# USB_Downloader_V1_2.net
KiCad netlist of a schematic drawn in Altium Designer
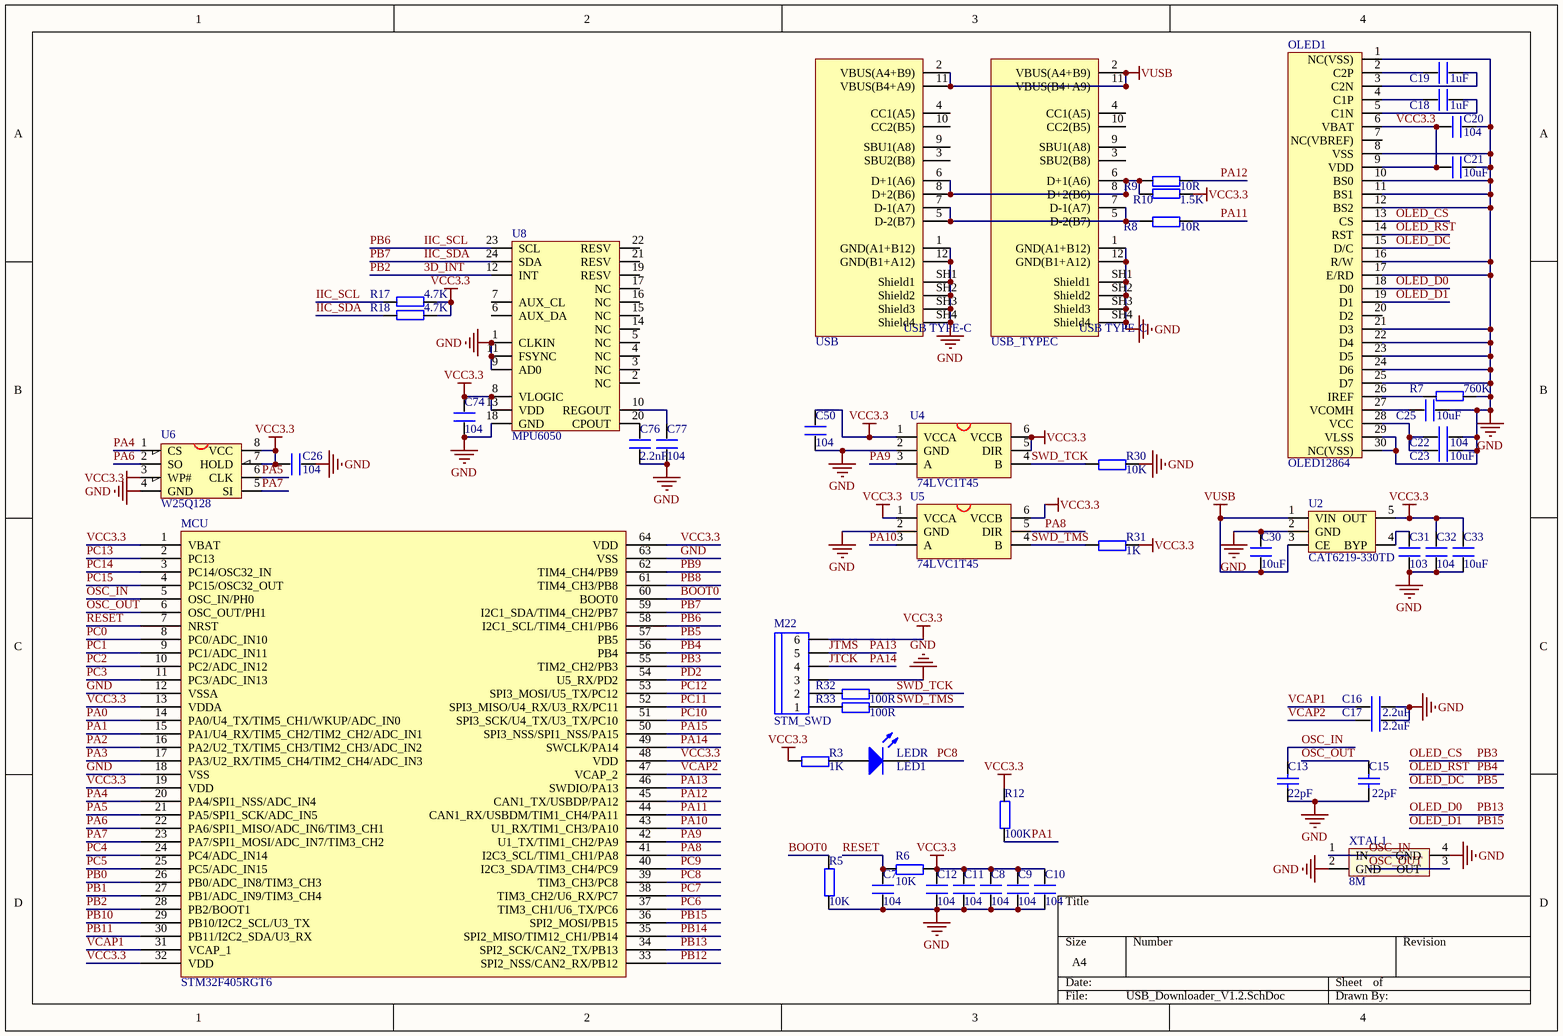
[diagram p0: USB_Downloader_V1.2.SchDoc]

(export (version "E")
  (design (tool "Eeschema 10.0.6"))
  (components
    (comp (ref "C7")
      (value "104")
      (footprint "C 0603_L")
      (libsource (lib "WarShip V3 STM32103封装库") (part "C"))
    )
    (comp (ref "C8")
      (value "104")
      (footprint "C 0603_L")
      (libsource (lib "WarShip V3 STM32103封装库") (part "C"))
    )
    (comp (ref "C9")
      (value "104")
      (footprint "C 0603_L")
      (libsource (lib "WarShip V3 STM32103封装库") (part "C"))
    )
    (comp (ref "C10")
      (value "104")
      (footprint "C 0603_L")
      (libsource (lib "WarShip V3 STM32103封装库") (part "C"))
    )
    (comp (ref "C11")
      (value "104")
      (footprint "C 0603_L")
      (libsource (lib "WarShip V3 STM32103封装库") (part "C"))
    )
    (comp (ref "C12")
      (value "104")
      (footprint "C 0603_L")
      (libsource (lib "WarShip V3 STM32103封装库") (part "C"))
    )
    (comp (ref "C13") (value "22pF") (footprint "C 0603_L") (libsource (lib "L476") (part "CAP")))
    (comp (ref "C15") (value "22pF") (footprint "C 0603_L") (libsource (lib "L476") (part "CAP")))
    (comp (ref "C16")
      (value "2.2uF")
      (footprint "C 0603_L")
      (libsource (lib "WarShip V3 STM32103封装库") (part "C"))
    )
    (comp (ref "C17")
      (value "2.2uF")
      (footprint "C 0603_L")
      (libsource (lib "WarShip V3 STM32103封装库") (part "C"))
    )
    (comp (ref "C18")
      (value "1uF")
      (footprint "C 0603_L")
      (libsource (lib "WarShip V3 STM32103封装库") (part "C"))
    )
    (comp (ref "C19")
      (value "1uF")
      (footprint "C 0603_L")
      (libsource (lib "WarShip V3 STM32103封装库") (part "C"))
    )
    (comp (ref "C20")
      (value "104")
      (footprint "C 0603_L")
      (libsource (lib "WarShip V3 STM32103封装库") (part "C"))
    )
    (comp (ref "C21")
      (value "10uF")
      (footprint "C 0603_L")
      (libsource (lib "WarShip V3 STM32103封装库") (part "C"))
    )
    (comp (ref "C22")
      (value "104")
      (footprint "C 0603_L")
      (libsource (lib "WarShip V3 STM32103封装库") (part "C"))
    )
    (comp (ref "C23")
      (value "10uF")
      (footprint "C 0603_L")
      (libsource (lib "WarShip V3 STM32103封装库") (part "C"))
    )
    (comp (ref "C25")
      (value "10uF")
      (footprint "C 0603_L")
      (libsource (lib "WarShip V3 STM32103封装库") (part "C"))
    )
    (comp (ref "C26")
      (value "104")
      (footprint "C 0603_L")
      (libsource (lib "WarShip V3 STM32103封装库") (part "C"))
    )
    (comp (ref "C30")
      (value "10uF")
      (footprint "C 0603_L")
      (libsource (lib "WarShip V3 STM32103封装库") (part "C"))
    )
    (comp (ref "C31")
      (value "103")
      (footprint "C 0603_L")
      (libsource (lib "WarShip V3 STM32103封装库") (part "C"))
    )
    (comp (ref "C32")
      (value "104")
      (footprint "C 0603_L")
      (libsource (lib "WarShip V3 STM32103封装库") (part "C"))
    )
    (comp (ref "C33")
      (value "10uF")
      (footprint "C 0603_L")
      (libsource (lib "WarShip V3 STM32103封装库") (part "C"))
    )
    (comp (ref "C50")
      (value "104")
      (footprint "C 0603_L")
      (libsource (lib "WarShip V3 STM32103封装库") (part "C"))
    )
    (comp (ref "C74") (value "104") (footprint "C 0603_L") (libsource (lib "MYCOMLIB") (part "C")))
    (comp (ref "C76") (value "2.2nF") (footprint "C 0603_L") (libsource (lib "MYCOMLIB") (part "C")))
    (comp (ref "C77") (value "104") (footprint "C 0603_L") (libsource (lib "MYCOMLIB") (part "C")))
    (comp (ref "LEDR")
      (value "LED1")
      (footprint "LED 0805B")
      (description "Typical RED, GREEN, YELLOW, AMBER GaAs LED")
      (fields (field (name "PUBLISHER") "Altium Limited"))
      (libsource (lib "阿波罗STM32F4&F7底板封装库") (part "LED2"))
    )
    (comp (ref "M22") (value "STM_SWD") (footprint "SH1.0-6P") (libsource (lib "MiniFly ") (part "HEAD6")))
    (comp (ref "MCU")
      (value "STM32F405RGT6")
      (footprint "LQFP64 10X10_L")
      (description "Flaah:256/RAM:48/IO:51")
      (libsource (lib "ATKF405 V1.1") (part "STM32F405RGT6"))
    )
    (comp (ref "OLED1")
      (value "OLED12864")
      (footprint "OLED_0.96")
      (libsource (lib "OLED模块封装库") (part "OLED12864"))
    )
    (comp (ref "R3")
      (value "1K")
      (footprint "R 0603_L")
      (libsource (lib "WarShip V3 STM32103封装库") (part "R"))
    )
    (comp (ref "R5")
      (value "10K")
      (footprint "R 0603_L")
      (libsource (lib "WarShip V3 STM32103封装库") (part "R"))
    )
    (comp (ref "R6")
      (value "10K")
      (footprint "R 0603_L")
      (libsource (lib "WarShip V3 STM32103封装库") (part "R"))
    )
    (comp (ref "R7")
      (value "760K")
      (footprint "R 0603_L")
      (libsource (lib "WarShip V3 STM32103封装库") (part "R"))
    )
    (comp (ref "R8")
      (value "10R")
      (footprint "R 0603_L")
      (libsource (lib "WarShip V3 STM32103封装库") (part "R"))
    )
    (comp (ref "R9")
      (value "10R")
      (footprint "R 0603_L")
      (libsource (lib "WarShip V3 STM32103封装库") (part "R"))
    )
    (comp (ref "R10")
      (value "1.5K")
      (footprint "R 0603_L")
      (libsource (lib "WarShip V3 STM32103封装库") (part "R"))
    )
    (comp (ref "R12")
      (value "100K")
      (footprint "R 0603_L")
      (libsource (lib "WarShip V3 STM32103封装库") (part "R"))
    )
    (comp (ref "R17")
      (value "4.7K")
      (footprint "R 0603_L")
      (libsource (lib "WarShip V3 STM32103封装库") (part "R"))
    )
    (comp (ref "R18")
      (value "4.7K")
      (footprint "R 0603_L")
      (libsource (lib "WarShip V3 STM32103封装库") (part "R"))
    )
    (comp (ref "R30")
      (value "10K")
      (footprint "R 0603_L")
      (libsource (lib "WarShip V3 STM32103封装库") (part "R"))
    )
    (comp (ref "R31")
      (value "1K")
      (footprint "R 0603_L")
      (libsource (lib "WarShip V3 STM32103封装库") (part "R"))
    )
    (comp (ref "R32")
      (value "100R")
      (footprint "R 0603_L")
      (libsource (lib "WarShip V3 STM32103封装库") (part "R"))
    )
    (comp (ref "R33")
      (value "100R")
      (footprint "R 0603_L")
      (libsource (lib "WarShip V3 STM32103封装库") (part "R"))
    )
    (comp (ref "U2")
      (value "CAT6219-330TD")
      (footprint "SOT23-5L")
      (description "3.3V 500mA LDO")
      (libsource (lib "STM32H743核心板封装库") (part "CAT6219-330TD"))
    )
    (comp (ref "U4")
      (value "74LVC1T45")
      (footprint "SOT363-6L")
      (description "1路双向电平转换")
      (libsource (lib "LovelessingSch") (part "74LVC1T45"))
    )
    (comp (ref "U5")
      (value "74LVC1T45")
      (footprint "SOT363-6L")
      (description "1路双向电平转换")
      (libsource (lib "LovelessingSch") (part "74LVC1T45"))
    )
    (comp (ref "U6")
      (value "W25Q128")
      (footprint "SOP8W_L")
      (description "W25X16;SST25VF016;MX25L1605")
      (libsource (lib "WarShip V3 STM32103封装库") (part "W25X16"))
    )
    (comp (ref "U8")
      (value "MPU6050")
      (footprint "QFN24 4x4_N")
      (description "9轴运动处理传感器")
      (libsource (lib "ALIENTEK_COMPONENT") (part "MPU6050"))
    )
    (comp (ref "USB")
      (value "USB TypeC")
      (footprint "USB Type-C")
      (description "12P TypeC 母座")
      (libsource (lib "ESP32_Weather") (part "USB Type-C"))
    )
    (comp (ref "USB_TYPEC")
      (value "USB TypeC")
      (footprint "USB Type-C")
      (description "12P TypeC 母座")
      (libsource (lib "ESP32_Weather") (part "USB Type-C"))
    )
    (comp (ref "XTAL1")
      (value "8M")
      (footprint "XTAL3225   无源")
      (description "无源贴片晶振")
      (libsource (lib "REMOTOR") (part "XTAL-无源贴片"))
    )
  )
  (nets
    (net (code "1") (name "/3D_INT") (class "Default")
      (node (ref "MCU") (pin "28") (pinfunction "PB2/BOOT1_28") (pintype "passive"))
      (node (ref "U8") (pin "12") (pinfunction "INT_12") (pintype "passive"))
    )
    (net (code "2") (name "/BOOT0") (class "Default")
      (node (ref "MCU") (pin "60") (pinfunction "BOOT0_60") (pintype "passive"))
      (node (ref "R5") (pin "2") (pintype "passive"))
    )
    (net (code "3") (name "/IIC_SCL") (class "Default")
      (node (ref "MCU") (pin "58") (pinfunction "I2C1_SCL/TIM4_CH1/PB6_58") (pintype "passive"))
      (node (ref "R17") (pin "2") (pintype "passive"))
      (node (ref "U8") (pin "23") (pinfunction "SCL_23") (pintype "passive"))
    )
    (net (code "4") (name "/IIC_SDA") (class "Default")
      (node (ref "MCU") (pin "59") (pinfunction "I2C1_SDA/TIM4_CH2/PB7_59") (pintype "passive"))
      (node (ref "R18") (pin "2") (pintype "passive"))
      (node (ref "U8") (pin "24") (pinfunction "SDA_24") (pintype "passive"))
    )
    (net (code "5") (name "/JTCK") (class "Default")
      (node (ref "M22") (pin "4") (pinfunction "4_4") (pintype "passive"))
      (node (ref "MCU") (pin "49") (pinfunction "SWCLK/PA14_49") (pintype "passive"))
    )
    (net (code "6") (name "/JTMS") (class "Default")
      (node (ref "M22") (pin "5") (pinfunction "5_5") (pintype "passive"))
      (node (ref "MCU") (pin "46") (pinfunction "SWDIO/PA13_46") (pintype "passive"))
    )
    (net (code "7") (name "/OLED_CS") (class "Default")
      (node (ref "MCU") (pin "55") (pinfunction "TIM2_CH2/PB3_55") (pintype "passive"))
      (node (ref "OLED1") (pin "13") (pinfunction "CS_13") (pintype "passive"))
    )
    (net (code "8") (name "/OLED_D0") (class "Default")
      (node (ref "MCU") (pin "34") (pinfunction "SPI2_SCK/CAN2_TX/PB13_34") (pintype "passive"))
      (node (ref "OLED1") (pin "18") (pinfunction "D0_18") (pintype "passive"))
    )
    (net (code "9") (name "/OLED_D1") (class "Default")
      (node (ref "MCU") (pin "36") (pinfunction "SPI2_MOSI/PB15_36") (pintype "passive"))
      (node (ref "OLED1") (pin "19") (pinfunction "D1_19") (pintype "passive"))
    )
    (net (code "10") (name "/OLED_DC") (class "Default")
      (node (ref "MCU") (pin "57") (pinfunction "PB5_57") (pintype "passive"))
      (node (ref "OLED1") (pin "15") (pinfunction "D/C_15") (pintype "passive"))
    )
    (net (code "11") (name "/OLED_RST") (class "Default")
      (node (ref "MCU") (pin "56") (pinfunction "PB4_56") (pintype "passive"))
      (node (ref "OLED1") (pin "14") (pinfunction "RST_14") (pintype "passive"))
    )
    (net (code "12") (name "/OSC_IN") (class "Default")
      (node (ref "C13") (pin "2") (pinfunction "2_2") (pintype "passive"))
      (node (ref "MCU") (pin "5") (pinfunction "OSC_IN/PH0_5") (pintype "passive"))
      (node (ref "XTAL1") (pin "1") (pinfunction "IN_1") (pintype "passive"))
    )
    (net (code "13") (name "/OSC_OUT") (class "Default")
      (node (ref "C15") (pin "2") (pinfunction "2_2") (pintype "passive"))
      (node (ref "MCU") (pin "6") (pinfunction "OSC_OUT/PH1_6") (pintype "passive"))
      (node (ref "XTAL1") (pin "3") (pinfunction "OUT_3") (pintype "passive"))
    )
    (net (code "14") (name "/PA0") (class "Default")
      (node (ref "MCU") (pin "14") (pinfunction "PA0/U4_TX/TIM5_CH1/WKUP/ADC_IN0_14") (pintype "passive"))
    )
    (net (code "15") (name "/PA1") (class "Default")
      (node (ref "MCU") (pin "15") (pinfunction "PA1/U4_RX/TIM5_CH2/TIM2_CH2/ADC_IN1_15") (pintype "passive"))
      (node (ref "R12") (pin "1") (pintype "passive"))
    )
    (net (code "16") (name "/PA2") (class "Default")
      (node (ref "MCU") (pin "16") (pinfunction "PA2/U2_TX/TIM5_CH3/TIM2_CH3/ADC_IN2_16") (pintype "passive"))
    )
    (net (code "17") (name "/PA3") (class "Default")
      (node (ref "MCU") (pin "17") (pinfunction "PA3/U2_RX/TIM5_CH4/TIM2_CH4/ADC_IN3_17") (pintype "passive"))
    )
    (net (code "18") (name "/PA4") (class "Default")
      (node (ref "MCU") (pin "20") (pinfunction "PA4/SPI1_NSS/ADC_IN4_20") (pintype "passive"))
      (node (ref "U6") (pin "1") (pinfunction "CS_1") (pintype "passive"))
    )
    (net (code "19") (name "/PA5") (class "Default")
      (node (ref "MCU") (pin "21") (pinfunction "PA5/SPI1_SCK/ADC_IN5_21") (pintype "passive"))
      (node (ref "U6") (pin "6") (pinfunction "CLK_6") (pintype "passive"))
    )
    (net (code "20") (name "/PA6") (class "Default")
      (node (ref "MCU") (pin "22") (pinfunction "PA6/SPI1_MISO/ADC_IN6/TIM3_CH1_22") (pintype "passive"))
      (node (ref "U6") (pin "2") (pinfunction "SO_2") (pintype "passive"))
    )
    (net (code "21") (name "/PA7") (class "Default")
      (node (ref "MCU") (pin "23") (pinfunction "PA7/SPI1_MOSI/ADC_IN7/TIM3_CH2_23") (pintype "passive"))
      (node (ref "U6") (pin "5") (pinfunction "SI_5") (pintype "passive"))
    )
    (net (code "22") (name "/PA8") (class "Default")
      (node (ref "MCU") (pin "41") (pinfunction "I2C3_SCL/TIM1_CH1/PA8_41") (pintype "passive"))
      (node (ref "U5") (pin "5") (pinfunction "DIR_5") (pintype "passive"))
    )
    (net (code "23") (name "/PA9") (class "Default")
      (node (ref "MCU") (pin "42") (pinfunction "U1_TX/TIM1_CH2/PA9_42") (pintype "passive"))
      (node (ref "U4") (pin "3") (pinfunction "A_3") (pintype "passive"))
    )
    (net (code "24") (name "/PA10") (class "Default")
      (node (ref "MCU") (pin "43") (pinfunction "U1_RX/TIM1_CH3/PA10_43") (pintype "passive"))
      (node (ref "U5") (pin "3") (pinfunction "A_3") (pintype "passive"))
    )
    (net (code "25") (name "/PA11") (class "Default")
      (node (ref "MCU") (pin "44") (pinfunction "CAN1_RX/USBDM/TIM1_CH4/PA11_44") (pintype "passive"))
      (node (ref "R8") (pin "2") (pintype "passive"))
    )
    (net (code "26") (name "/PA12") (class "Default")
      (node (ref "MCU") (pin "45") (pinfunction "CAN1_TX/USBDP/PA12_45") (pintype "passive"))
      (node (ref "R9") (pin "2") (pintype "passive"))
    )
    (net (code "27") (name "/PA15") (class "Default")
      (node (ref "MCU") (pin "50") (pinfunction "SPI3_NSS/SPI1_NSS/PA15_50") (pintype "passive"))
    )
    (net (code "28") (name "/PB0") (class "Default")
      (node (ref "MCU") (pin "26") (pinfunction "PB0/ADC_IN8/TIM3_CH3_26") (pintype "passive"))
    )
    (net (code "29") (name "/PB1") (class "Default")
      (node (ref "MCU") (pin "27") (pinfunction "PB1/ADC_IN9/TIM3_CH4_27") (pintype "passive"))
    )
    (net (code "30") (name "/PB8") (class "Default")
      (node (ref "MCU") (pin "61") (pinfunction "TIM4_CH3/PB8_61") (pintype "passive"))
    )
    (net (code "31") (name "/PB9") (class "Default")
      (node (ref "MCU") (pin "62") (pinfunction "TIM4_CH4/PB9_62") (pintype "passive"))
    )
    (net (code "32") (name "/PB10") (class "Default")
      (node (ref "MCU") (pin "29") (pinfunction "PB10/I2C2_SCL/U3_TX_29") (pintype "passive"))
    )
    (net (code "33") (name "/PB11") (class "Default")
      (node (ref "MCU") (pin "30") (pinfunction "PB11/I2C2_SDA/U3_RX_30") (pintype "passive"))
    )
    (net (code "34") (name "/PB12") (class "Default")
      (node (ref "MCU") (pin "33") (pinfunction "SPI2_NSS/CAN2_RX/PB12_33") (pintype "passive"))
    )
    (net (code "35") (name "/PB14") (class "Default")
      (node (ref "MCU") (pin "35") (pinfunction "SPI2_MISO/TIM12_CH1/PB14_35") (pintype "passive"))
    )
    (net (code "36") (name "/PC0") (class "Default")
      (node (ref "MCU") (pin "8") (pinfunction "PC0/ADC_IN10_8") (pintype "passive"))
    )
    (net (code "37") (name "/PC1") (class "Default")
      (node (ref "MCU") (pin "9") (pinfunction "PC1/ADC_IN11_9") (pintype "passive"))
    )
    (net (code "38") (name "/PC2") (class "Default")
      (node (ref "MCU") (pin "10") (pinfunction "PC2/ADC_IN12_10") (pintype "passive"))
    )
    (net (code "39") (name "/PC3") (class "Default")
      (node (ref "MCU") (pin "11") (pinfunction "PC3/ADC_IN13_11") (pintype "passive"))
    )
    (net (code "40") (name "/PC4") (class "Default")
      (node (ref "MCU") (pin "24") (pinfunction "PC4/ADC_IN14_24") (pintype "passive"))
    )
    (net (code "41") (name "/PC5") (class "Default")
      (node (ref "MCU") (pin "25") (pinfunction "PC5/ADC_IN15_25") (pintype "passive"))
    )
    (net (code "42") (name "/PC6") (class "Default")
      (node (ref "MCU") (pin "37") (pinfunction "TIM3_CH1/U6_TX/PC6_37") (pintype "passive"))
    )
    (net (code "43") (name "/PC7") (class "Default")
      (node (ref "MCU") (pin "38") (pinfunction "TIM3_CH2/U6_RX/PC7_38") (pintype "passive"))
    )
    (net (code "44") (name "/PC8") (class "Default")
      (node (ref "LEDR") (pin "2") (pinfunction "K_2") (pintype "passive"))
      (node (ref "MCU") (pin "39") (pinfunction "TIM3_CH3/PC8_39") (pintype "passive"))
    )
    (net (code "45") (name "/PC9") (class "Default")
      (node (ref "MCU") (pin "40") (pinfunction "I2C3_SDA/TIM3_CH4/PC9_40") (pintype "passive"))
    )
    (net (code "46") (name "/PC10") (class "Default")
      (node (ref "MCU") (pin "51") (pinfunction "SPI3_SCK/U4_TX/U3_TX/PC10_51") (pintype "passive"))
    )
    (net (code "47") (name "/PC11") (class "Default")
      (node (ref "MCU") (pin "52") (pinfunction "SPI3_MISO/U4_RX/U3_RX/PC11_52") (pintype "passive"))
    )
    (net (code "48") (name "/PC12") (class "Default")
      (node (ref "MCU") (pin "53") (pinfunction "SPI3_MOSI/U5_TX/PC12_53") (pintype "passive"))
    )
    (net (code "49") (name "/PC13") (class "Default")
      (node (ref "MCU") (pin "2") (pinfunction "PC13_2") (pintype "passive"))
    )
    (net (code "50") (name "/PC14") (class "Default")
      (node (ref "MCU") (pin "3") (pinfunction "PC14/OSC32_IN_3") (pintype "passive"))
    )
    (net (code "51") (name "/PC15") (class "Default")
      (node (ref "MCU") (pin "4") (pinfunction "PC15/OSC32_OUT_4") (pintype "passive"))
    )
    (net (code "52") (name "/PD2") (class "Default")
      (node (ref "MCU") (pin "54") (pinfunction "U5_RX/PD2_54") (pintype "passive"))
    )
    (net (code "53") (name "/RESET") (class "Default")
      (node (ref "C7") (pin "2") (pintype "passive"))
      (node (ref "MCU") (pin "7") (pinfunction "NRST_7") (pintype "passive"))
      (node (ref "R6") (pin "1") (pintype "passive"))
    )
    (net (code "54") (name "/SWD_TCK") (class "Default")
      (node (ref "R30") (pin "1") (pintype "passive"))
      (node (ref "R32") (pin "2") (pintype "passive"))
      (node (ref "U4") (pin "4") (pinfunction "B_4") (pintype "passive"))
    )
    (net (code "55") (name "/SWD_TMS") (class "Default")
      (node (ref "R31") (pin "1") (pintype "passive"))
      (node (ref "R33") (pin "2") (pintype "passive"))
      (node (ref "U5") (pin "4") (pinfunction "B_4") (pintype "passive"))
    )
    (net (code "56") (name "/VCAP1") (class "Default")
      (node (ref "C16") (pin "2") (pintype "passive"))
      (node (ref "MCU") (pin "31") (pinfunction "VCAP_1_31") (pintype "passive"))
    )
    (net (code "57") (name "/VCAP2") (class "Default")
      (node (ref "C17") (pin "2") (pintype "passive"))
      (node (ref "MCU") (pin "47") (pinfunction "VCAP_2_47") (pintype "passive"))
    )
    (net (code "58") (name "GND") (class "Default")
      (node (ref "C10") (pin "1") (pintype "passive"))
      (node (ref "C11") (pin "1") (pintype "passive"))
      (node (ref "C12") (pin "1") (pintype "passive"))
      (node (ref "C13") (pin "1") (pinfunction "1_1") (pintype "passive"))
      (node (ref "C15") (pin "1") (pinfunction "1_1") (pintype "passive"))
      (node (ref "C16") (pin "1") (pintype "passive"))
      (node (ref "C17") (pin "1") (pintype "passive"))
      (node (ref "C20") (pin "1") (pintype "passive"))
      (node (ref "C21") (pin "1") (pintype "passive"))
      (node (ref "C22") (pin "1") (pintype "passive"))
      (node (ref "C23") (pin "1") (pintype "passive"))
      (node (ref "C25") (pin "1") (pintype "passive"))
      (node (ref "C26") (pin "2") (pintype "passive"))
      (node (ref "C30") (pin "2") (pintype "passive"))
      (node (ref "C31") (pin "1") (pintype "passive"))
      (node (ref "C32") (pin "1") (pintype "passive"))
      (node (ref "C33") (pin "1") (pintype "passive"))
      (node (ref "C50") (pin "1") (pintype "passive"))
      (node (ref "C7") (pin "1") (pintype "passive"))
      (node (ref "C74") (pin "1") (pintype "passive"))
      (node (ref "C76") (pin "1") (pintype "passive"))
      (node (ref "C77") (pin "2") (pintype "passive"))
      (node (ref "C8") (pin "1") (pintype "passive"))
      (node (ref "C9") (pin "1") (pintype "passive"))
      (node (ref "M22") (pin "3") (pinfunction "3_3") (pintype "passive"))
      (node (ref "MCU") (pin "12") (pinfunction "VSSA_12") (pintype "passive"))
      (node (ref "MCU") (pin "18") (pinfunction "VSS_18") (pintype "passive"))
      (node (ref "MCU") (pin "63") (pinfunction "VSS_63") (pintype "passive"))
      (node (ref "OLED1") (pin "1") (pinfunction "NC(VSS)_1") (pintype "passive"))
      (node (ref "OLED1") (pin "10") (pinfunction "BS0_10") (pintype "passive"))
      (node (ref "OLED1") (pin "11") (pinfunction "BS1_11") (pintype "passive"))
      (node (ref "OLED1") (pin "12") (pinfunction "BS2_12") (pintype "passive"))
      (node (ref "OLED1") (pin "16") (pinfunction "R/W_16") (pintype "passive"))
      (node (ref "OLED1") (pin "17") (pinfunction "E/RD_17") (pintype "passive"))
      (node (ref "OLED1") (pin "21") (pinfunction "D3_21") (pintype "passive"))
      (node (ref "OLED1") (pin "22") (pinfunction "D4_22") (pintype "passive"))
      (node (ref "OLED1") (pin "23") (pinfunction "D5_23") (pintype "passive"))
      (node (ref "OLED1") (pin "24") (pinfunction "D6_24") (pintype "passive"))
      (node (ref "OLED1") (pin "25") (pinfunction "D7_25") (pintype "passive"))
      (node (ref "OLED1") (pin "29") (pinfunction "VLSS_29") (pintype "passive"))
      (node (ref "OLED1") (pin "30") (pinfunction "NC(VSS)_30") (pintype "passive"))
      (node (ref "OLED1") (pin "8") (pinfunction "VSS_8") (pintype "passive"))
      (node (ref "R30") (pin "2") (pintype "passive"))
      (node (ref "R5") (pin "1") (pintype "passive"))
      (node (ref "R7") (pin "1") (pintype "passive"))
      (node (ref "U2") (pin "2") (pinfunction "GND_2") (pintype "passive"))
      (node (ref "U4") (pin "2") (pinfunction "GND_2") (pintype "passive"))
      (node (ref "U5") (pin "2") (pinfunction "GND_2") (pintype "passive"))
      (node (ref "U6") (pin "4") (pinfunction "GND_4") (pintype "passive"))
      (node (ref "U8") (pin "1") (pinfunction "CLKIN_1") (pintype "passive"))
      (node (ref "U8") (pin "11") (pinfunction "FSYNC_11") (pintype "passive"))
      (node (ref "U8") (pin "18") (pinfunction "GND_18") (pintype "passive"))
      (node (ref "U8") (pin "9") (pinfunction "AD0_9") (pintype "passive"))
      (node (ref "USB") (pin "1") (pinfunction "GND(A1+B12)_1") (pintype "passive"))
      (node (ref "USB") (pin "12") (pinfunction "GND(B1+A12)_12") (pintype "passive"))
      (node (ref "USB") (pin "SH1") (pinfunction "Shield1_SH1") (pintype "passive"))
      (node (ref "USB") (pin "SH2") (pinfunction "Shield2_SH2") (pintype "passive"))
      (node (ref "USB") (pin "SH3") (pinfunction "Shield3_SH3") (pintype "passive"))
      (node (ref "USB") (pin "SH4") (pinfunction "Shield4_SH4") (pintype "passive"))
      (node (ref "USB_TYPEC") (pin "1") (pinfunction "GND(A1+B12)_1") (pintype "passive"))
      (node (ref "USB_TYPEC") (pin "12") (pinfunction "GND(B1+A12)_12") (pintype "passive"))
      (node (ref "USB_TYPEC") (pin "SH1") (pinfunction "Shield1_SH1") (pintype "passive"))
      (node (ref "USB_TYPEC") (pin "SH2") (pinfunction "Shield2_SH2") (pintype "passive"))
      (node (ref "USB_TYPEC") (pin "SH3") (pinfunction "Shield3_SH3") (pintype "passive"))
      (node (ref "USB_TYPEC") (pin "SH4") (pinfunction "Shield4_SH4") (pintype "passive"))
      (node (ref "XTAL1") (pin "2") (pinfunction "GND_2") (pintype "passive"))
      (node (ref "XTAL1") (pin "4") (pinfunction "GND_4") (pintype "passive"))
    )
    (net (code "59") (name "Net-(LEDR-A)") (class "Default")
      (node (ref "LEDR") (pin "1") (pinfunction "A_1") (pintype "passive"))
      (node (ref "R3") (pin "2") (pintype "passive"))
    )
    (net (code "60") (name "Net-(M22-Pad1)") (class "Default")
      (node (ref "M22") (pin "1") (pinfunction "1_1") (pintype "passive"))
      (node (ref "R33") (pin "1") (pintype "passive"))
    )
    (net (code "61") (name "Net-(M22-Pad2)") (class "Default")
      (node (ref "M22") (pin "2") (pinfunction "2_2") (pintype "passive"))
      (node (ref "R32") (pin "1") (pintype "passive"))
    )
    (net (code "62") (name "Net-(OLED1-C1N)") (class "Default")
      (node (ref "C18") (pin "1") (pintype "passive"))
      (node (ref "OLED1") (pin "5") (pinfunction "C1N_5") (pintype "passive"))
    )
    (net (code "63") (name "Net-(OLED1-C1P)") (class "Default")
      (node (ref "C18") (pin "2") (pintype "passive"))
      (node (ref "OLED1") (pin "4") (pinfunction "C1P_4") (pintype "passive"))
    )
    (net (code "64") (name "Net-(OLED1-C2N)") (class "Default")
      (node (ref "C19") (pin "1") (pintype "passive"))
      (node (ref "OLED1") (pin "3") (pinfunction "C2N_3") (pintype "passive"))
    )
    (net (code "65") (name "Net-(OLED1-C2P)") (class "Default")
      (node (ref "C19") (pin "2") (pintype "passive"))
      (node (ref "OLED1") (pin "2") (pinfunction "C2P_2") (pintype "passive"))
    )
    (net (code "66") (name "Net-(OLED1-IREF)") (class "Default")
      (node (ref "OLED1") (pin "26") (pinfunction "IREF_26") (pintype "passive"))
      (node (ref "R7") (pin "2") (pintype "passive"))
    )
    (net (code "67") (name "Net-(OLED1-VCC)") (class "Default")
      (node (ref "C22") (pin "2") (pintype "passive"))
      (node (ref "C23") (pin "2") (pintype "passive"))
      (node (ref "OLED1") (pin "28") (pinfunction "VCC_28") (pintype "passive"))
    )
    (net (code "68") (name "Net-(OLED1-VCOMH)") (class "Default")
      (node (ref "C25") (pin "2") (pintype "passive"))
      (node (ref "OLED1") (pin "27") (pinfunction "VCOMH_27") (pintype "passive"))
    )
    (net (code "69") (name "Net-(U2-BYP)") (class "Default")
      (node (ref "C31") (pin "2") (pintype "passive"))
      (node (ref "U2") (pin "4") (pinfunction "BYP_4") (pintype "passive"))
    )
    (net (code "70") (name "Net-(U8-CPOUT)") (class "Default")
      (node (ref "C76") (pin "2") (pintype "passive"))
      (node (ref "U8") (pin "20") (pinfunction "CPOUT_20") (pintype "passive"))
    )
    (net (code "71") (name "Net-(U8-REGOUT)") (class "Default")
      (node (ref "C77") (pin "1") (pintype "passive"))
      (node (ref "U8") (pin "10") (pinfunction "REGOUT_10") (pintype "passive"))
    )
    (net (code "72") (name "Net-(USB-D+1(A6))") (class "Default")
      (node (ref "R10") (pin "2") (pintype "passive"))
      (node (ref "R9") (pin "1") (pintype "passive"))
      (node (ref "USB") (pin "6") (pinfunction "D+1(A6)_6") (pintype "passive"))
      (node (ref "USB") (pin "8") (pinfunction "D+2(B6)_8") (pintype "passive"))
      (node (ref "USB_TYPEC") (pin "6") (pinfunction "D+1(A6)_6") (pintype "passive"))
      (node (ref "USB_TYPEC") (pin "8") (pinfunction "D+2(B6)_8") (pintype "passive"))
    )
    (net (code "73") (name "Net-(USB-D-1(A7))") (class "Default")
      (node (ref "R8") (pin "1") (pintype "passive"))
      (node (ref "USB") (pin "5") (pinfunction "D-2(B7)_5") (pintype "passive"))
      (node (ref "USB") (pin "7") (pinfunction "D-1(A7)_7") (pintype "passive"))
      (node (ref "USB_TYPEC") (pin "5") (pinfunction "D-2(B7)_5") (pintype "passive"))
      (node (ref "USB_TYPEC") (pin "7") (pinfunction "D-1(A7)_7") (pintype "passive"))
    )
    (net (code "74") (name "VCC3.3") (class "Default")
      (node (ref "C10") (pin "2") (pintype "passive"))
      (node (ref "C11") (pin "2") (pintype "passive"))
      (node (ref "C12") (pin "2") (pintype "passive"))
      (node (ref "C20") (pin "2") (pintype "passive"))
      (node (ref "C21") (pin "2") (pintype "passive"))
      (node (ref "C26") (pin "1") (pintype "passive"))
      (node (ref "C32") (pin "2") (pintype "passive"))
      (node (ref "C33") (pin "2") (pintype "passive"))
      (node (ref "C50") (pin "2") (pintype "passive"))
      (node (ref "C74") (pin "2") (pintype "passive"))
      (node (ref "C8") (pin "2") (pintype "passive"))
      (node (ref "C9") (pin "2") (pintype "passive"))
      (node (ref "M22") (pin "6") (pinfunction "6_6") (pintype "passive"))
      (node (ref "MCU") (pin "1") (pinfunction "VBAT_1") (pintype "passive"))
      (node (ref "MCU") (pin "13") (pinfunction "VDDA_13") (pintype "passive"))
      (node (ref "MCU") (pin "19") (pinfunction "VDD_19") (pintype "passive"))
      (node (ref "MCU") (pin "32") (pinfunction "VDD_32") (pintype "passive"))
      (node (ref "MCU") (pin "48") (pinfunction "VDD_48") (pintype "passive"))
      (node (ref "MCU") (pin "64") (pinfunction "VDD_64") (pintype "passive"))
      (node (ref "OLED1") (pin "6") (pinfunction "VBAT_6") (pintype "passive"))
      (node (ref "OLED1") (pin "9") (pinfunction "VDD_9") (pintype "passive"))
      (node (ref "R10") (pin "1") (pintype "passive"))
      (node (ref "R12") (pin "2") (pintype "passive"))
      (node (ref "R17") (pin "1") (pintype "passive"))
      (node (ref "R18") (pin "1") (pintype "passive"))
      (node (ref "R3") (pin "1") (pintype "passive"))
      (node (ref "R31") (pin "2") (pintype "passive"))
      (node (ref "R6") (pin "2") (pintype "passive"))
      (node (ref "U2") (pin "5") (pinfunction "OUT_5") (pintype "passive"))
      (node (ref "U4") (pin "1") (pinfunction "VCCA_1") (pintype "passive"))
      (node (ref "U4") (pin "5") (pinfunction "DIR_5") (pintype "passive"))
      (node (ref "U4") (pin "6") (pinfunction "VCCB_6") (pintype "passive"))
      (node (ref "U5") (pin "1") (pinfunction "VCCA_1") (pintype "passive"))
      (node (ref "U5") (pin "6") (pinfunction "VCCB_6") (pintype "passive"))
      (node (ref "U6") (pin "3") (pinfunction "WP#_3") (pintype "passive"))
      (node (ref "U6") (pin "7") (pinfunction "HOLD_7") (pintype "passive"))
      (node (ref "U6") (pin "8") (pinfunction "VCC_8") (pintype "passive"))
      (node (ref "U8") (pin "13") (pinfunction "VDD_13") (pintype "passive"))
      (node (ref "U8") (pin "8") (pinfunction "VLOGIC_8") (pintype "passive"))
    )
    (net (code "75") (name "VUSB") (class "Default")
      (node (ref "C30") (pin "1") (pintype "passive"))
      (node (ref "U2") (pin "1") (pinfunction "VIN_1") (pintype "passive"))
      (node (ref "U2") (pin "3") (pinfunction "CE_3") (pintype "passive"))
      (node (ref "USB") (pin "11") (pinfunction "VBUS(B4+A9)_11") (pintype "passive"))
      (node (ref "USB") (pin "2") (pinfunction "VBUS(A4+B9)_2") (pintype "passive"))
      (node (ref "USB_TYPEC") (pin "11") (pinfunction "VBUS(B4+A9)_11") (pintype "passive"))
      (node (ref "USB_TYPEC") (pin "2") (pinfunction "VBUS(A4+B9)_2") (pintype "passive"))
    )
    (net (code "76") (name "unconnected-(OLED1-D2-Pad20)") (class "Default")
      (node (ref "OLED1") (pin "20") (pinfunction "D2_20") (pintype "passive"))
    )
    (net (code "77") (name "unconnected-(OLED1-NC(VBREF)-Pad7)") (class "Default")
      (node (ref "OLED1") (pin "7") (pinfunction "NC(VBREF)_7") (pintype "passive"))
    )
    (net (code "78") (name "unconnected-(U8-AUX_CL-Pad7)") (class "Default")
      (node (ref "U8") (pin "7") (pinfunction "AUX_CL_7") (pintype "passive"))
    )
    (net (code "79") (name "unconnected-(U8-AUX_DA-Pad6)") (class "Default")
      (node (ref "U8") (pin "6") (pinfunction "AUX_DA_6") (pintype "passive"))
    )
    (net (code "80") (name "unconnected-(U8-NC-Pad2)") (class "Default")
      (node (ref "U8") (pin "2") (pinfunction "NC_2") (pintype "passive"))
    )
    (net (code "81") (name "unconnected-(U8-NC-Pad3)") (class "Default")
      (node (ref "U8") (pin "3") (pinfunction "NC_3") (pintype "passive"))
    )
    (net (code "82") (name "unconnected-(U8-NC-Pad4)") (class "Default")
      (node (ref "U8") (pin "4") (pinfunction "NC_4") (pintype "passive"))
    )
    (net (code "83") (name "unconnected-(U8-NC-Pad5)") (class "Default")
      (node (ref "U8") (pin "5") (pinfunction "NC_5") (pintype "passive"))
    )
    (net (code "84") (name "unconnected-(U8-NC-Pad14)") (class "Default")
      (node (ref "U8") (pin "14") (pinfunction "NC_14") (pintype "passive"))
    )
    (net (code "85") (name "unconnected-(U8-NC-Pad15)") (class "Default")
      (node (ref "U8") (pin "15") (pinfunction "NC_15") (pintype "passive"))
    )
    (net (code "86") (name "unconnected-(U8-NC-Pad16)") (class "Default")
      (node (ref "U8") (pin "16") (pinfunction "NC_16") (pintype "passive"))
    )
    (net (code "87") (name "unconnected-(U8-NC-Pad17)") (class "Default")
      (node (ref "U8") (pin "17") (pinfunction "NC_17") (pintype "passive"))
    )
    (net (code "88") (name "unconnected-(U8-RESV-Pad19)") (class "Default")
      (node (ref "U8") (pin "19") (pinfunction "RESV_19") (pintype "passive"))
    )
    (net (code "89") (name "unconnected-(U8-RESV-Pad21)") (class "Default")
      (node (ref "U8") (pin "21") (pinfunction "RESV_21") (pintype "passive"))
    )
    (net (code "90") (name "unconnected-(U8-RESV-Pad22)") (class "Default")
      (node (ref "U8") (pin "22") (pinfunction "RESV_22") (pintype "passive"))
    )
    (net (code "91") (name "unconnected-(USB-CC1(A5)-Pad4)") (class "Default")
      (node (ref "USB") (pin "4") (pinfunction "CC1(A5)_4") (pintype "passive"))
    )
    (net (code "92") (name "unconnected-(USB-CC2(B5)-Pad10)") (class "Default")
      (node (ref "USB") (pin "10") (pinfunction "CC2(B5)_10") (pintype "passive"))
    )
    (net (code "93") (name "unconnected-(USB-SBU1(A8)-Pad9)") (class "Default")
      (node (ref "USB") (pin "9") (pinfunction "SBU1(A8)_9") (pintype "passive"))
    )
    (net (code "94") (name "unconnected-(USB-SBU2(B8)-Pad3)") (class "Default")
      (node (ref "USB") (pin "3") (pinfunction "SBU2(B8)_3") (pintype "passive"))
    )
    (net (code "95") (name "unconnected-(USB_TYPEC-CC1(A5)-Pad4)") (class "Default")
      (node (ref "USB_TYPEC") (pin "4") (pinfunction "CC1(A5)_4") (pintype "passive"))
    )
    (net (code "96") (name "unconnected-(USB_TYPEC-CC2(B5)-Pad10)") (class "Default")
      (node (ref "USB_TYPEC") (pin "10") (pinfunction "CC2(B5)_10") (pintype "passive"))
    )
    (net (code "97") (name "unconnected-(USB_TYPEC-SBU1(A8)-Pad9)") (class "Default")
      (node (ref "USB_TYPEC") (pin "9") (pinfunction "SBU1(A8)_9") (pintype "passive"))
    )
    (net (code "98") (name "unconnected-(USB_TYPEC-SBU2(B8)-Pad3)") (class "Default")
      (node (ref "USB_TYPEC") (pin "3") (pinfunction "SBU2(B8)_3") (pintype "passive"))
    )
  )
)
